# Flash_EEPROM_Memory.net
KiCad netlist of a schematic drawn in Altium Designer
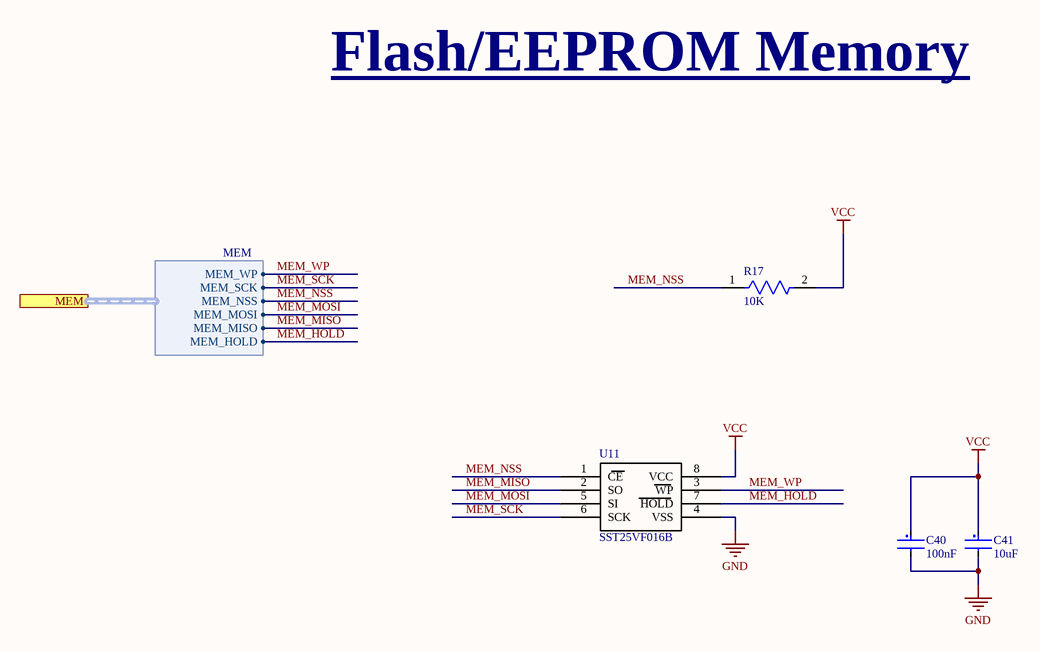
[diagram p0: Flash_EEPROM_Memory.SchDoc]

(export (version "E")
  (design (tool "Eeschema 10.0.6"))
  (components
    (comp (ref "C40")
      (value "100nF")
      (footprint "Samsung_CL31_IPC_A_1206")
      (description "CAP CER 0.1UF 50V X7R 1206, ±10% 50V Ceramic Capacitor X7R 1206 (3216 Metric)")
      (libsource (lib "DMD_Card") (part "CL31B104KBCNFNC"))
    )
    (comp (ref "C41")
      (value "10uF")
      (footprint "Samsung_CL31_IPC_A_1206")
      (description "CAP CER 10UF 6.3V X5R 1206, ±10% 6.3V Ceramic Capacitor X5R 1206 (3216 Metric)")
      (libsource (lib "DMD_Card") (part "CL31A106KQHNNWE"))
    )
    (comp (ref "R17")
      (value "10K")
      (footprint "YAGEO_RC1206-0_65_IPC_A")
      (description "1 ±5% 0.25W, 1/4W Chip Resistor 1206 (3216 Metric) Moisture Resistant Thick Film")
      (libsource (lib "DMD_Card") (part "RC1206JR-071KL"))
    )
    (comp (ref "U11")
      (value "SST25VF016B")
      (footprint "SOIC-8")
      (libsource (lib "DMD_Card") (part "SST25VF016B"))
    )
  )
  (nets
    (net (code "2") (name "/MEM_HOLD") (class "Default")
      (node (ref "U11") (pin "7") (pinfunction "HOLD_7") (pintype "passive"))
    )
    (net (code "3") (name "/MEM_MISO") (class "Default")
      (node (ref "U11") (pin "2") (pinfunction "SO_2") (pintype "passive"))
    )
    (net (code "4") (name "/MEM_MOSI") (class "Default")
      (node (ref "U11") (pin "5") (pinfunction "SI_5") (pintype "passive"))
    )
    (net (code "5") (name "/MEM_NSS") (class "Default")
      (node (ref "R17") (pin "1") (pinfunction "1_1") (pintype "passive"))
      (node (ref "U11") (pin "1") (pinfunction "CE_1") (pintype "passive"))
    )
    (net (code "6") (name "/MEM_SCK") (class "Default")
      (node (ref "U11") (pin "6") (pinfunction "SCK_6") (pintype "passive"))
    )
    (net (code "7") (name "/MEM_WP") (class "Default")
      (node (ref "U11") (pin "3") (pinfunction "WP_3") (pintype "passive"))
    )
    (net (code "9") (name "GND") (class "Default")
      (node (ref "C40") (pin "2") (pinfunction "2_2") (pintype "passive"))
      (node (ref "C41") (pin "2") (pinfunction "2_2") (pintype "passive"))
      (node (ref "U11") (pin "4") (pinfunction "VSS_4") (pintype "passive"))
    )
    (net (code "10") (name "VCC") (class "Default")
      (node (ref "C40") (pin "1") (pinfunction "1_1") (pintype "passive"))
      (node (ref "C41") (pin "1") (pinfunction "1_1") (pintype "passive"))
      (node (ref "R17") (pin "2") (pinfunction "2_2") (pintype "passive"))
      (node (ref "U11") (pin "8") (pinfunction "VCC_8") (pintype "passive"))
    )
  )
)
